# Config.net
KiCad netlist of a schematic drawn in Altium Designer
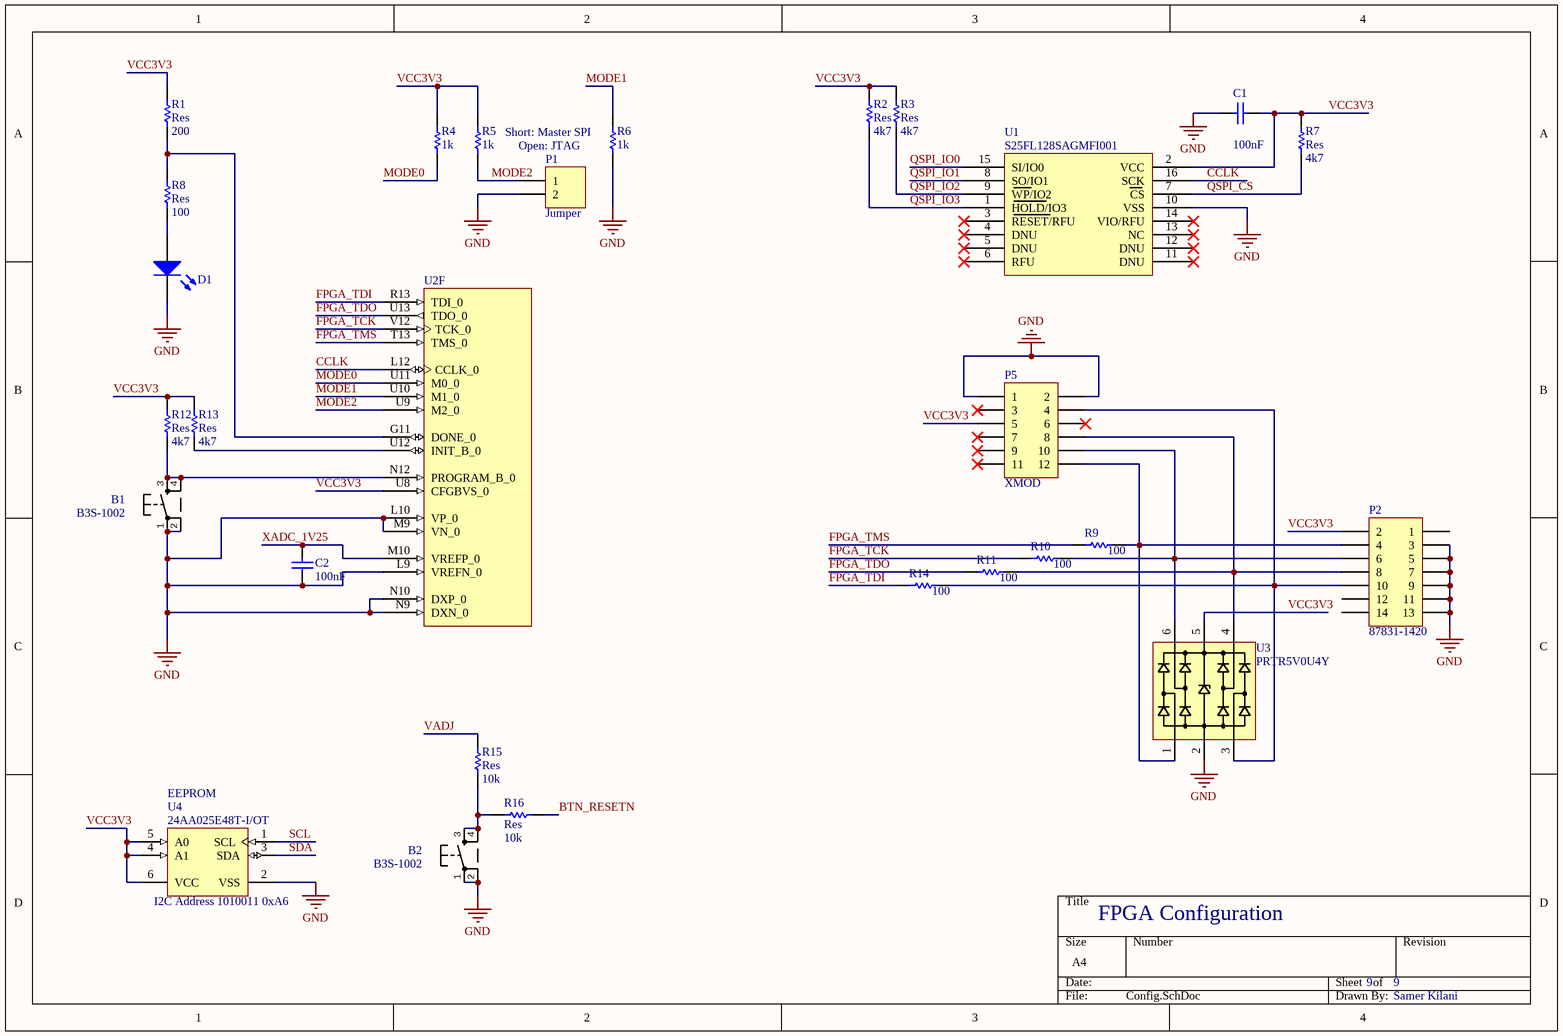
[diagram p0: Config.SchDoc]

(export (version "E")
  (design (tool "Eeschema 10.0.6"))
  (components
    (comp (ref "B1") (value "B3S-1002") (footprint "B3S-1002") (libsource (lib "atfclib") (part "TS42")))
    (comp (ref "B2") (value "B3S-1002") (footprint "B3S-1002") (libsource (lib "atfclib") (part "TS42")))
    (comp (ref "C1")
      (value "100nF")
      (footprint "C0603")
      (description "Capacitor")
      (fields (field (name "Comment") "Cap") (field (name "PUBLISHER") "Altium Limited"))
      (libsource (lib "atfclib") (part "Cap"))
    )
    (comp (ref "C2")
      (value "100nF")
      (footprint "C0402")
      (description "Capacitor")
      (fields (field (name "Comment") "Cap") (field (name "PUBLISHER") "Altium Limited"))
      (libsource (lib "atfclib") (part "Cap"))
    )
    (comp (ref "D1")
      (value "KPT-1608EC")
      (footprint "KP-1608QBC-D")
      (fields (field (name "PUBLISHER") "Altium Limited"))
      (libsource (lib "atfclib") (part "LED"))
    )
    (comp (ref "P1")
      (value "Jumper")
      (footprint "HDR1X2")
      (description "Header, 2-Pin")
      (fields (field (name "PUBLISHER") "Altium Limited"))
      (libsource (lib "Miscellaneous Connectors") (part "Header 2"))
    )
    (comp (ref "P2")
      (value "87831-1420")
      (footprint "87831-1420")
      (description "Header, 7-Pin, Dual row")
      (fields (field (name "PUBLISHER") "Altium Limited"))
      (libsource (lib "Miscellaneous Connectors") (part "Header 7X2"))
    )
    (comp (ref "P5")
      (value "XMOD")
      (footprint "HDR2X6")
      (description "Header, 6-Pin, Dual row")
      (fields (field (name "PUBLISHER") "Altium Limited"))
      (libsource (lib "Miscellaneous Connectors") (part "Header 6X2"))
    )
    (comp (ref "R1")
      (value "Res")
      (footprint "R0603")
      (description "Resistor")
      (fields (field (name "ALTIUM_VALUE") "200"))
      (libsource (lib "atfclib") (part "Res"))
    )
    (comp (ref "R2")
      (value "Res")
      (footprint "R0603")
      (description "Resistor")
      (fields (field (name "ALTIUM_VALUE") "4k7"))
      (libsource (lib "atfclib") (part "Res"))
    )
    (comp (ref "R3")
      (value "Res")
      (footprint "R0603")
      (description "Resistor")
      (fields (field (name "ALTIUM_VALUE") "4k7"))
      (libsource (lib "atfclib") (part "Res"))
    )
    (comp (ref "R4")
      (value "1k")
      (footprint "R0402")
      (description "Resistor")
      (fields (field (name "Comment") "Res"))
      (libsource (lib "atfclib") (part "Res"))
    )
    (comp (ref "R5")
      (value "1k")
      (footprint "R0402")
      (description "Resistor")
      (fields (field (name "Comment") "Res"))
      (libsource (lib "atfclib") (part "Res"))
    )
    (comp (ref "R6")
      (value "1k")
      (footprint "R0402")
      (description "Resistor")
      (fields (field (name "Comment") "Res"))
      (libsource (lib "atfclib") (part "Res"))
    )
    (comp (ref "R7")
      (value "Res")
      (footprint "R0603")
      (description "Resistor")
      (fields (field (name "ALTIUM_VALUE") "4k7"))
      (libsource (lib "atfclib") (part "Res"))
    )
    (comp (ref "R8")
      (value "Res")
      (footprint "R0603")
      (description "Resistor")
      (fields (field (name "ALTIUM_VALUE") "100"))
      (libsource (lib "atfclib") (part "Res"))
    )
    (comp (ref "R9")
      (value "100")
      (footprint "R0402")
      (description "Resistor")
      (fields (field (name "Comment") "Res"))
      (libsource (lib "atfclib") (part "Res"))
    )
    (comp (ref "R10")
      (value "100")
      (footprint "R0402")
      (description "Resistor")
      (fields (field (name "Comment") "Res"))
      (libsource (lib "atfclib") (part "Res"))
    )
    (comp (ref "R11")
      (value "100")
      (footprint "R0402")
      (description "Resistor")
      (fields (field (name "Comment") "Res"))
      (libsource (lib "atfclib") (part "Res"))
    )
    (comp (ref "R12")
      (value "Res")
      (footprint "R0603")
      (description "Resistor")
      (fields (field (name "ALTIUM_VALUE") "4k7"))
      (libsource (lib "atfclib") (part "Res"))
    )
    (comp (ref "R13")
      (value "Res")
      (footprint "R0402")
      (description "Resistor")
      (fields (field (name "ALTIUM_VALUE") "4k7"))
      (libsource (lib "atfclib") (part "Res"))
    )
    (comp (ref "R14")
      (value "100")
      (footprint "R0402")
      (description "Resistor")
      (fields (field (name "Comment") "Res"))
      (libsource (lib "atfclib") (part "Res"))
    )
    (comp (ref "R15")
      (value "Res")
      (footprint "R0603")
      (description "Resistor")
      (fields (field (name "ALTIUM_VALUE") "10k"))
      (libsource (lib "atfclib") (part "Res"))
    )
    (comp (ref "R16")
      (value "Res")
      (footprint "R0603")
      (description "Resistor")
      (fields (field (name "ALTIUM_VALUE") "10k"))
      (libsource (lib "atfclib") (part "Res"))
    )
    (comp (ref "U1")
      (value "S25FL128SAGMFI001")
      (footprint "SOIC16")
      (libsource (lib "atfclib") (part "S25FL128SAGMFI001"))
    )
    (comp (ref "U2")
      (value "~")
      (footprint "FGG484")
      (description "Artix-7 FPGA, 250 User I/Os, 4 GTP, 484-Ball BGA, Speed Grade 1, Commercial Grade, Pb-Free")
      (fields (field (name "MANUFACTURER") "Xilinx") (field (name "PARTNUMBER") "XC7A35T-1FGG484C"))
      (libsource (lib "atfclib") (part "XC7A35T-1FGG484C"))
    )
    (comp (ref "U3")
      (value "PRTR5V0U4Y")
      (footprint "SOT363")
      (libsource (lib "atfclib") (part "PRTR5V0U4Y"))
    )
    (comp (ref "U4")
      (value "24AA025E48T-I/OT")
      (footprint "MCHP-SOT-23-OT6_N")
      (fields (field (name "MANUFACTURER") "Microchip"))
      (libsource (lib "atfclib") (part "24AA025E48T-I/OT"))
    )
  )
  (nets
    (net (code "1") (name "/BTN_RESETN") (class "Default")
      (node (ref "R16") (pin "1") (pinfunction "1_1") (pintype "passive"))
    )
    (net (code "2") (name "/CCLK") (class "Default")
      (node (ref "U1") (pin "16") (pinfunction "SCK_16") (pintype "passive"))
      (node (ref "U2") (pin "L12") (pinfunction "CCLK_0_L12") (pintype "bidirectional"))
    )
    (net (code "3") (name "/FPGA_TCK") (class "Default")
      (node (ref "R10") (pin "1") (pinfunction "1_1") (pintype "passive"))
      (node (ref "U2") (pin "V12") (pinfunction "TCK_0_V12") (pintype "input"))
    )
    (net (code "4") (name "/FPGA_TDI") (class "Default")
      (node (ref "R14") (pin "1") (pinfunction "1_1") (pintype "passive"))
      (node (ref "U2") (pin "R13") (pinfunction "TDI_0_R13") (pintype "input"))
    )
    (net (code "5") (name "/FPGA_TDO") (class "Default")
      (node (ref "R11") (pin "1") (pinfunction "1_1") (pintype "passive"))
      (node (ref "U2") (pin "U13") (pinfunction "TDO_0_U13") (pintype "output"))
    )
    (net (code "6") (name "/FPGA_TMS") (class "Default")
      (node (ref "R9") (pin "1") (pinfunction "1_1") (pintype "passive"))
      (node (ref "U2") (pin "T13") (pinfunction "TMS_0_T13") (pintype "input"))
    )
    (net (code "7") (name "/MODE0") (class "Default")
      (node (ref "R4") (pin "1") (pinfunction "1_1") (pintype "passive"))
      (node (ref "U2") (pin "U11") (pinfunction "M0_0_U11") (pintype "input"))
    )
    (net (code "8") (name "/MODE1") (class "Default")
      (node (ref "R6") (pin "2") (pinfunction "2_2") (pintype "passive"))
      (node (ref "U2") (pin "U10") (pinfunction "M1_0_U10") (pintype "input"))
    )
    (net (code "9") (name "/MODE2") (class "Default")
      (node (ref "P1") (pin "1") (pinfunction "1_1") (pintype "passive"))
      (node (ref "R5") (pin "1") (pinfunction "1_1") (pintype "passive"))
      (node (ref "U2") (pin "U9") (pinfunction "M2_0_U9") (pintype "input"))
    )
    (net (code "10") (name "/QSPI_CS") (class "Default")
      (node (ref "R7") (pin "1") (pinfunction "1_1") (pintype "passive"))
      (node (ref "U1") (pin "7") (pinfunction "CS_7") (pintype "passive"))
    )
    (net (code "11") (name "/QSPI_IO0") (class "Default")
      (node (ref "U1") (pin "15") (pinfunction "SI/IO0_15") (pintype "passive"))
    )
    (net (code "12") (name "/QSPI_IO1") (class "Default")
      (node (ref "U1") (pin "8") (pinfunction "SO/IO1_8") (pintype "passive"))
    )
    (net (code "13") (name "/QSPI_IO2") (class "Default")
      (node (ref "R3") (pin "1") (pinfunction "1_1") (pintype "passive"))
      (node (ref "U1") (pin "9") (pinfunction "WP/IO2_9") (pintype "passive"))
    )
    (net (code "14") (name "/QSPI_IO3") (class "Default")
      (node (ref "R2") (pin "1") (pinfunction "1_1") (pintype "passive"))
      (node (ref "U1") (pin "1") (pinfunction "HOLD/IO3_1") (pintype "passive"))
    )
    (net (code "15") (name "/SCL") (class "Default")
      (node (ref "U4") (pin "1") (pinfunction "SCL_1") (pintype "input"))
    )
    (net (code "16") (name "/SDA") (class "Default")
      (node (ref "U4") (pin "3") (pinfunction "SDA_3") (pintype "bidirectional"))
    )
    (net (code "17") (name "/VADJ") (class "Default")
      (node (ref "R15") (pin "2") (pinfunction "2_2") (pintype "passive"))
    )
    (net (code "18") (name "/VCC3V3") (class "Default")
      (node (ref "C1") (pin "2") (pinfunction "2_2") (pintype "passive"))
      (node (ref "P2") (pin "2") (pinfunction "2_2") (pintype "passive"))
      (node (ref "P5") (pin "5") (pinfunction "5_5") (pintype "passive"))
      (node (ref "R1") (pin "2") (pinfunction "2_2") (pintype "passive"))
      (node (ref "R12") (pin "2") (pinfunction "2_2") (pintype "passive"))
      (node (ref "R13") (pin "2") (pinfunction "2_2") (pintype "passive"))
      (node (ref "R2") (pin "2") (pinfunction "2_2") (pintype "passive"))
      (node (ref "R3") (pin "2") (pinfunction "2_2") (pintype "passive"))
      (node (ref "R4") (pin "2") (pinfunction "2_2") (pintype "passive"))
      (node (ref "R5") (pin "2") (pinfunction "2_2") (pintype "passive"))
      (node (ref "R7") (pin "2") (pinfunction "2_2") (pintype "passive"))
      (node (ref "U1") (pin "2") (pinfunction "VCC_2") (pintype "passive"))
      (node (ref "U2") (pin "U8") (pinfunction "CFGBVS_0_U8") (pintype "input"))
      (node (ref "U3") (pin "5") (pinfunction "5_5") (pintype "passive"))
      (node (ref "U4") (pin "4") (pinfunction "A1_4") (pintype "input"))
      (node (ref "U4") (pin "5") (pinfunction "A0_5") (pintype "input"))
      (node (ref "U4") (pin "6") (pinfunction "VCC_6") (pintype "power_in"))
    )
    (net (code "19") (name "/XADC_1V25") (class "Default")
      (node (ref "C2") (pin "2") (pinfunction "2_2") (pintype "passive"))
      (node (ref "U2") (pin "M10") (pinfunction "VREFP_0_M10") (pintype "input"))
    )
    (net (code "20") (name "GND") (class "Default")
      (node (ref "B1") (pin "1") (pinfunction "1_1") (pintype "passive"))
      (node (ref "B1") (pin "2") (pinfunction "2_2") (pintype "passive"))
      (node (ref "B2") (pin "1") (pinfunction "1_1") (pintype "passive"))
      (node (ref "B2") (pin "2") (pinfunction "2_2") (pintype "passive"))
      (node (ref "C1") (pin "1") (pinfunction "1_1") (pintype "passive"))
      (node (ref "C2") (pin "1") (pinfunction "1_1") (pintype "passive"))
      (node (ref "D1") (pin "2") (pinfunction "K_2") (pintype "passive"))
      (node (ref "P1") (pin "2") (pinfunction "2_2") (pintype "passive"))
      (node (ref "P2") (pin "11") (pinfunction "11_11") (pintype "passive"))
      (node (ref "P2") (pin "13") (pinfunction "13_13") (pintype "passive"))
      (node (ref "P2") (pin "3") (pinfunction "3_3") (pintype "passive"))
      (node (ref "P2") (pin "5") (pinfunction "5_5") (pintype "passive"))
      (node (ref "P2") (pin "7") (pinfunction "7_7") (pintype "passive"))
      (node (ref "P2") (pin "9") (pinfunction "9_9") (pintype "passive"))
      (node (ref "P5") (pin "1") (pinfunction "1_1") (pintype "passive"))
      (node (ref "P5") (pin "2") (pinfunction "2_2") (pintype "passive"))
      (node (ref "R6") (pin "1") (pinfunction "1_1") (pintype "passive"))
      (node (ref "U1") (pin "10") (pinfunction "VSS_10") (pintype "passive"))
      (node (ref "U2") (pin "L10") (pinfunction "VP_0_L10") (pintype "input"))
      (node (ref "U2") (pin "L9") (pinfunction "VREFN_0_L9") (pintype "input"))
      (node (ref "U2") (pin "M9") (pinfunction "VN_0_M9") (pintype "input"))
      (node (ref "U2") (pin "N10") (pinfunction "DXP_0_N10") (pintype "input"))
      (node (ref "U2") (pin "N9") (pinfunction "DXN_0_N9") (pintype "input"))
      (node (ref "U3") (pin "2") (pinfunction "2_2") (pintype "passive"))
      (node (ref "U4") (pin "2") (pinfunction "VSS_2") (pintype "power_in"))
    )
    (net (code "21") (name "Net-(B2-Pad3)") (class "Default")
      (node (ref "B2") (pin "3") (pinfunction "3_3") (pintype "passive"))
      (node (ref "B2") (pin "4") (pinfunction "4_4") (pintype "passive"))
      (node (ref "R15") (pin "1") (pinfunction "1_1") (pintype "passive"))
      (node (ref "R16") (pin "2") (pinfunction "2_2") (pintype "passive"))
    )
    (net (code "22") (name "Net-(D1-A)") (class "Default")
      (node (ref "D1") (pin "1") (pinfunction "A_1") (pintype "passive"))
      (node (ref "R8") (pin "1") (pinfunction "1_1") (pintype "passive"))
    )
    (net (code "23") (name "Net-(P2-Pad4)") (class "Default")
      (node (ref "P2") (pin "4") (pinfunction "4_4") (pintype "passive"))
      (node (ref "P5") (pin "12") (pinfunction "12_12") (pintype "passive"))
      (node (ref "R9") (pin "2") (pinfunction "2_2") (pintype "passive"))
      (node (ref "U3") (pin "1") (pinfunction "1_1") (pintype "passive"))
    )
    (net (code "24") (name "Net-(P2-Pad6)") (class "Default")
      (node (ref "P2") (pin "6") (pinfunction "6_6") (pintype "passive"))
      (node (ref "P5") (pin "10") (pinfunction "10_10") (pintype "passive"))
      (node (ref "R10") (pin "2") (pinfunction "2_2") (pintype "passive"))
      (node (ref "U3") (pin "6") (pinfunction "6_6") (pintype "passive"))
    )
    (net (code "25") (name "Net-(P2-Pad8)") (class "Default")
      (node (ref "P2") (pin "8") (pinfunction "8_8") (pintype "passive"))
      (node (ref "P5") (pin "8") (pinfunction "8_8") (pintype "passive"))
      (node (ref "R11") (pin "2") (pinfunction "2_2") (pintype "passive"))
      (node (ref "U3") (pin "4") (pinfunction "4_4") (pintype "passive"))
    )
    (net (code "26") (name "Net-(P2-Pad10)") (class "Default")
      (node (ref "P2") (pin "10") (pinfunction "10_10") (pintype "passive"))
      (node (ref "P5") (pin "4") (pinfunction "4_4") (pintype "passive"))
      (node (ref "R14") (pin "2") (pinfunction "2_2") (pintype "passive"))
      (node (ref "U3") (pin "3") (pinfunction "3_3") (pintype "passive"))
    )
    (net (code "27") (name "Net-(U2F-DONE_0)") (class "Default")
      (node (ref "R1") (pin "1") (pinfunction "1_1") (pintype "passive"))
      (node (ref "R8") (pin "2") (pinfunction "2_2") (pintype "passive"))
      (node (ref "U2") (pin "G11") (pinfunction "DONE_0_G11") (pintype "bidirectional"))
    )
    (net (code "28") (name "Net-(U2F-INIT_B_0)") (class "Default")
      (node (ref "R13") (pin "1") (pinfunction "1_1") (pintype "passive"))
      (node (ref "U2") (pin "U12") (pinfunction "INIT_B_0_U12") (pintype "bidirectional"))
    )
    (net (code "29") (name "Net-(U2F-PROGRAM_B_0)") (class "Default")
      (node (ref "B1") (pin "3") (pinfunction "3_3") (pintype "passive"))
      (node (ref "B1") (pin "4") (pinfunction "4_4") (pintype "passive"))
      (node (ref "R12") (pin "1") (pinfunction "1_1") (pintype "passive"))
      (node (ref "U2") (pin "N12") (pinfunction "PROGRAM_B_0_N12") (pintype "input"))
    )
    (net (code "30") (name "unconnected-(P2-Pad1)") (class "Default")
      (node (ref "P2") (pin "1") (pinfunction "1_1") (pintype "passive"))
    )
    (net (code "31") (name "unconnected-(P2-Pad12)") (class "Default")
      (node (ref "P2") (pin "12") (pinfunction "12_12") (pintype "passive"))
    )
    (net (code "32") (name "unconnected-(P2-Pad14)") (class "Default")
      (node (ref "P2") (pin "14") (pinfunction "14_14") (pintype "passive"))
    )
    (net (code "33") (name "unconnected-(P5-Pad3)") (class "Default")
      (node (ref "P5") (pin "3") (pinfunction "3_3") (pintype "passive+no_connect"))
    )
    (net (code "34") (name "unconnected-(P5-Pad6)") (class "Default")
      (node (ref "P5") (pin "6") (pinfunction "6_6") (pintype "passive+no_connect"))
    )
    (net (code "35") (name "unconnected-(P5-Pad7)") (class "Default")
      (node (ref "P5") (pin "7") (pinfunction "7_7") (pintype "passive+no_connect"))
    )
    (net (code "36") (name "unconnected-(P5-Pad9)") (class "Default")
      (node (ref "P5") (pin "9") (pinfunction "9_9") (pintype "passive+no_connect"))
    )
    (net (code "37") (name "unconnected-(P5-Pad11)") (class "Default")
      (node (ref "P5") (pin "11") (pinfunction "11_11") (pintype "passive+no_connect"))
    )
    (net (code "38") (name "unconnected-(U1-DNU-Pad4)") (class "Default")
      (node (ref "U1") (pin "4") (pinfunction "DNU_4") (pintype "passive+no_connect"))
    )
    (net (code "39") (name "unconnected-(U1-DNU-Pad5)") (class "Default")
      (node (ref "U1") (pin "5") (pinfunction "DNU_5") (pintype "passive+no_connect"))
    )
    (net (code "40") (name "unconnected-(U1-DNU-Pad11)") (class "Default")
      (node (ref "U1") (pin "11") (pinfunction "DNU_11") (pintype "passive+no_connect"))
    )
    (net (code "41") (name "unconnected-(U1-DNU-Pad12)") (class "Default")
      (node (ref "U1") (pin "12") (pinfunction "DNU_12") (pintype "passive+no_connect"))
    )
    (net (code "42") (name "unconnected-(U1-NC-Pad13)") (class "Default")
      (node (ref "U1") (pin "13") (pinfunction "NC_13") (pintype "passive+no_connect"))
    )
    (net (code "43") (name "unconnected-(U1-RESET{slash}RFU-Pad3)") (class "Default")
      (node (ref "U1") (pin "3") (pinfunction "RESET/RFU_3") (pintype "passive+no_connect"))
    )
    (net (code "44") (name "unconnected-(U1-RFU-Pad6)") (class "Default")
      (node (ref "U1") (pin "6") (pinfunction "RFU_6") (pintype "passive+no_connect"))
    )
    (net (code "45") (name "unconnected-(U1-VIO{slash}RFU-Pad14)") (class "Default")
      (node (ref "U1") (pin "14") (pinfunction "VIO/RFU_14") (pintype "passive+no_connect"))
    )
  )
)
